# DSP_GPIO_Part2.net
KiCad netlist of a schematic drawn in Altium Designer
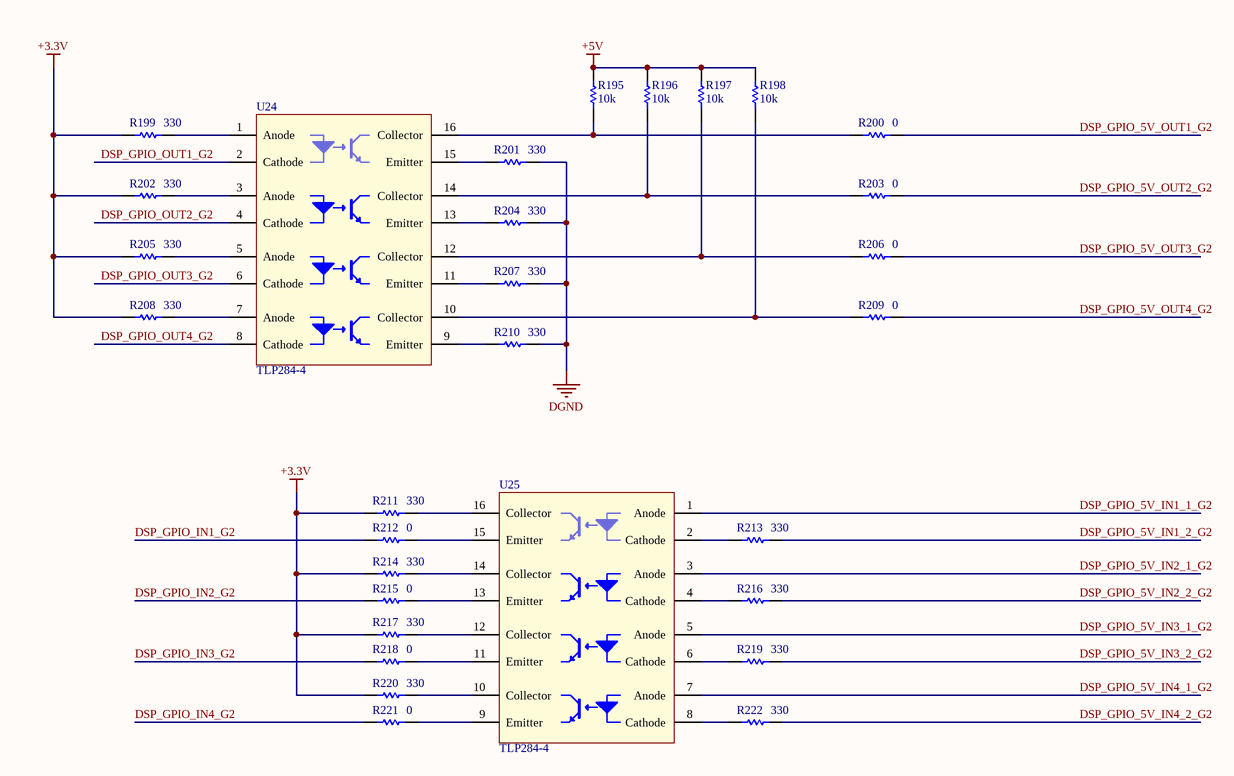
[diagram p0: DSP_GPIO_Part2.SchDoc]

(export (version "E")
  (design (tool "Eeschema 10.0.6"))
  (components
    (comp (ref "R195")
      (value "10k")
      (footprint "1608[0603]")
      (description "Resistor")
      (fields (field (name "Comment") "Res1") (field (name "PUBLISHER") "Altium Limited"))
      (libsource (lib "Miscellaneous Devices") (part "Res1"))
    )
    (comp (ref "R196")
      (value "10k")
      (footprint "1608[0603]")
      (description "Resistor")
      (fields (field (name "Comment") "Res1") (field (name "PUBLISHER") "Altium Limited"))
      (libsource (lib "Miscellaneous Devices") (part "Res1"))
    )
    (comp (ref "R197")
      (value "10k")
      (footprint "1608[0603]")
      (description "Resistor")
      (fields (field (name "Comment") "Res1") (field (name "PUBLISHER") "Altium Limited"))
      (libsource (lib "Miscellaneous Devices") (part "Res1"))
    )
    (comp (ref "R198")
      (value "10k")
      (footprint "1608[0603]")
      (description "Resistor")
      (fields (field (name "Comment") "Res1") (field (name "PUBLISHER") "Altium Limited"))
      (libsource (lib "Miscellaneous Devices") (part "Res1"))
    )
    (comp (ref "R199")
      (value "330")
      (footprint "1608[0603]")
      (description "Resistor")
      (fields (field (name "Comment") "Res1") (field (name "PUBLISHER") "Altium Limited"))
      (libsource (lib "Miscellaneous Devices") (part "Res1"))
    )
    (comp (ref "R200")
      (value "0")
      (footprint "1608[0603]")
      (description "Resistor")
      (fields (field (name "Comment") "Res1") (field (name "PUBLISHER") "Altium Limited"))
      (libsource (lib "Miscellaneous Devices") (part "Res1"))
    )
    (comp (ref "R201")
      (value "330")
      (footprint "1608[0603]")
      (description "Resistor")
      (fields (field (name "Comment") "Res1") (field (name "PUBLISHER") "Altium Limited"))
      (libsource (lib "Miscellaneous Devices") (part "Res1"))
    )
    (comp (ref "R202")
      (value "330")
      (footprint "1608[0603]")
      (description "Resistor")
      (fields (field (name "Comment") "Res1") (field (name "PUBLISHER") "Altium Limited"))
      (libsource (lib "Miscellaneous Devices") (part "Res1"))
    )
    (comp (ref "R203")
      (value "0")
      (footprint "1608[0603]")
      (description "Resistor")
      (fields (field (name "Comment") "Res1") (field (name "PUBLISHER") "Altium Limited"))
      (libsource (lib "Miscellaneous Devices") (part "Res1"))
    )
    (comp (ref "R204")
      (value "330")
      (footprint "1608[0603]")
      (description "Resistor")
      (fields (field (name "Comment") "Res1") (field (name "PUBLISHER") "Altium Limited"))
      (libsource (lib "Miscellaneous Devices") (part "Res1"))
    )
    (comp (ref "R205")
      (value "330")
      (footprint "1608[0603]")
      (description "Resistor")
      (fields (field (name "Comment") "Res1") (field (name "PUBLISHER") "Altium Limited"))
      (libsource (lib "Miscellaneous Devices") (part "Res1"))
    )
    (comp (ref "R206")
      (value "0")
      (footprint "1608[0603]")
      (description "Resistor")
      (fields (field (name "Comment") "Res1") (field (name "PUBLISHER") "Altium Limited"))
      (libsource (lib "Miscellaneous Devices") (part "Res1"))
    )
    (comp (ref "R207")
      (value "330")
      (footprint "1608[0603]")
      (description "Resistor")
      (fields (field (name "Comment") "Res1") (field (name "PUBLISHER") "Altium Limited"))
      (libsource (lib "Miscellaneous Devices") (part "Res1"))
    )
    (comp (ref "R208")
      (value "330")
      (footprint "1608[0603]")
      (description "Resistor")
      (fields (field (name "Comment") "Res1") (field (name "PUBLISHER") "Altium Limited"))
      (libsource (lib "Miscellaneous Devices") (part "Res1"))
    )
    (comp (ref "R209")
      (value "0")
      (footprint "1608[0603]")
      (description "Resistor")
      (fields (field (name "Comment") "Res1") (field (name "PUBLISHER") "Altium Limited"))
      (libsource (lib "Miscellaneous Devices") (part "Res1"))
    )
    (comp (ref "R210")
      (value "330")
      (footprint "1608[0603]")
      (description "Resistor")
      (fields (field (name "Comment") "Res1") (field (name "PUBLISHER") "Altium Limited"))
      (libsource (lib "Miscellaneous Devices") (part "Res1"))
    )
    (comp (ref "R211")
      (value "330")
      (footprint "1608[0603]")
      (description "Resistor")
      (fields (field (name "Comment") "Res1") (field (name "PUBLISHER") "Altium Limited"))
      (libsource (lib "Miscellaneous Devices") (part "Res1"))
    )
    (comp (ref "R212")
      (value "0")
      (footprint "1608[0603]")
      (description "Resistor")
      (fields (field (name "Comment") "Res1") (field (name "PUBLISHER") "Altium Limited"))
      (libsource (lib "Miscellaneous Devices") (part "Res1"))
    )
    (comp (ref "R213")
      (value "330")
      (footprint "1608[0603]")
      (description "Resistor")
      (fields (field (name "Comment") "Res1") (field (name "PUBLISHER") "Altium Limited"))
      (libsource (lib "Miscellaneous Devices") (part "Res1"))
    )
    (comp (ref "R214")
      (value "330")
      (footprint "1608[0603]")
      (description "Resistor")
      (fields (field (name "Comment") "Res1") (field (name "PUBLISHER") "Altium Limited"))
      (libsource (lib "Miscellaneous Devices") (part "Res1"))
    )
    (comp (ref "R215")
      (value "0")
      (footprint "1608[0603]")
      (description "Resistor")
      (fields (field (name "Comment") "Res1") (field (name "PUBLISHER") "Altium Limited"))
      (libsource (lib "Miscellaneous Devices") (part "Res1"))
    )
    (comp (ref "R216")
      (value "330")
      (footprint "1608[0603]")
      (description "Resistor")
      (fields (field (name "Comment") "Res1") (field (name "PUBLISHER") "Altium Limited"))
      (libsource (lib "Miscellaneous Devices") (part "Res1"))
    )
    (comp (ref "R217")
      (value "330")
      (footprint "1608[0603]")
      (description "Resistor")
      (fields (field (name "Comment") "Res1") (field (name "PUBLISHER") "Altium Limited"))
      (libsource (lib "Miscellaneous Devices") (part "Res1"))
    )
    (comp (ref "R218")
      (value "0")
      (footprint "1608[0603]")
      (description "Resistor")
      (fields (field (name "Comment") "Res1") (field (name "PUBLISHER") "Altium Limited"))
      (libsource (lib "Miscellaneous Devices") (part "Res1"))
    )
    (comp (ref "R219")
      (value "330")
      (footprint "1608[0603]")
      (description "Resistor")
      (fields (field (name "Comment") "Res1") (field (name "PUBLISHER") "Altium Limited"))
      (libsource (lib "Miscellaneous Devices") (part "Res1"))
    )
    (comp (ref "R220")
      (value "330")
      (footprint "1608[0603]")
      (description "Resistor")
      (fields (field (name "Comment") "Res1") (field (name "PUBLISHER") "Altium Limited"))
      (libsource (lib "Miscellaneous Devices") (part "Res1"))
    )
    (comp (ref "R221")
      (value "0")
      (footprint "1608[0603]")
      (description "Resistor")
      (fields (field (name "Comment") "Res1") (field (name "PUBLISHER") "Altium Limited"))
      (libsource (lib "Miscellaneous Devices") (part "Res1"))
    )
    (comp (ref "R222")
      (value "330")
      (footprint "1608[0603]")
      (description "Resistor")
      (fields (field (name "Comment") "Res1") (field (name "PUBLISHER") "Altium Limited"))
      (libsource (lib "Miscellaneous Devices") (part "Res1"))
    )
    (comp (ref "U24")
      (value "TLP284-4")
      (footprint "TLP284-4")
      (libsource (lib "DSP_FPGA_Lib") (part "TLP284-4"))
    )
    (comp (ref "U25")
      (value "TLP284-4")
      (footprint "TLP284-4")
      (libsource (lib "DSP_FPGA_Lib") (part "TLP284-4"))
    )
  )
  (nets
    (net (code "1") (name "+3.3V") (class "Default")
      (node (ref "R199") (pin "1") (pinfunction "1_1") (pintype "passive"))
      (node (ref "R202") (pin "1") (pinfunction "1_1") (pintype "passive"))
      (node (ref "R205") (pin "1") (pinfunction "1_1") (pintype "passive"))
      (node (ref "R208") (pin "1") (pinfunction "1_1") (pintype "passive"))
      (node (ref "R211") (pin "1") (pinfunction "1_1") (pintype "passive"))
      (node (ref "R214") (pin "1") (pinfunction "1_1") (pintype "passive"))
      (node (ref "R217") (pin "1") (pinfunction "1_1") (pintype "passive"))
      (node (ref "R220") (pin "1") (pinfunction "1_1") (pintype "passive"))
    )
    (net (code "2") (name "+5V") (class "Default")
      (node (ref "R195") (pin "2") (pinfunction "2_2") (pintype "passive"))
      (node (ref "R196") (pin "2") (pinfunction "2_2") (pintype "passive"))
      (node (ref "R197") (pin "2") (pinfunction "2_2") (pintype "passive"))
      (node (ref "R198") (pin "2") (pinfunction "2_2") (pintype "passive"))
    )
    (net (code "3") (name "/DSP_GPIO_5V_IN1_1_G2") (class "Default")
      (node (ref "U25") (pin "1") (pinfunction "Anode_1") (pintype "passive"))
    )
    (net (code "4") (name "/DSP_GPIO_5V_IN1_2_G2") (class "Default")
      (node (ref "R213") (pin "2") (pinfunction "2_2") (pintype "passive"))
    )
    (net (code "5") (name "/DSP_GPIO_5V_IN2_1_G2") (class "Default")
      (node (ref "U25") (pin "3") (pinfunction "Anode_3") (pintype "passive"))
    )
    (net (code "6") (name "/DSP_GPIO_5V_IN2_2_G2") (class "Default")
      (node (ref "R216") (pin "2") (pinfunction "2_2") (pintype "passive"))
    )
    (net (code "7") (name "/DSP_GPIO_5V_IN3_1_G2") (class "Default")
      (node (ref "U25") (pin "5") (pinfunction "Anode_5") (pintype "passive"))
    )
    (net (code "8") (name "/DSP_GPIO_5V_IN3_2_G2") (class "Default")
      (node (ref "R219") (pin "2") (pinfunction "2_2") (pintype "passive"))
    )
    (net (code "9") (name "/DSP_GPIO_5V_IN4_1_G2") (class "Default")
      (node (ref "U25") (pin "7") (pinfunction "Anode_7") (pintype "passive"))
    )
    (net (code "10") (name "/DSP_GPIO_5V_IN4_2_G2") (class "Default")
      (node (ref "R222") (pin "2") (pinfunction "2_2") (pintype "passive"))
    )
    (net (code "11") (name "/DSP_GPIO_5V_OUT1_G2") (class "Default")
      (node (ref "R200") (pin "2") (pinfunction "2_2") (pintype "passive"))
    )
    (net (code "12") (name "/DSP_GPIO_5V_OUT2_G2") (class "Default")
      (node (ref "R203") (pin "2") (pinfunction "2_2") (pintype "passive"))
    )
    (net (code "13") (name "/DSP_GPIO_5V_OUT3_G2") (class "Default")
      (node (ref "R206") (pin "2") (pinfunction "2_2") (pintype "passive"))
    )
    (net (code "14") (name "/DSP_GPIO_5V_OUT4_G2") (class "Default")
      (node (ref "R209") (pin "2") (pinfunction "2_2") (pintype "passive"))
    )
    (net (code "15") (name "/DSP_GPIO_IN1_G2") (class "Default")
      (node (ref "R212") (pin "1") (pinfunction "1_1") (pintype "passive"))
    )
    (net (code "16") (name "/DSP_GPIO_IN2_G2") (class "Default")
      (node (ref "R215") (pin "1") (pinfunction "1_1") (pintype "passive"))
    )
    (net (code "17") (name "/DSP_GPIO_IN3_G2") (class "Default")
      (node (ref "R218") (pin "1") (pinfunction "1_1") (pintype "passive"))
    )
    (net (code "18") (name "/DSP_GPIO_IN4_G2") (class "Default")
      (node (ref "R221") (pin "1") (pinfunction "1_1") (pintype "passive"))
    )
    (net (code "19") (name "/DSP_GPIO_OUT1_G2") (class "Default")
      (node (ref "U24") (pin "2") (pinfunction "Cathode_2") (pintype "passive"))
    )
    (net (code "20") (name "/DSP_GPIO_OUT2_G2") (class "Default")
      (node (ref "U24") (pin "4") (pinfunction "Cathode_4") (pintype "passive"))
    )
    (net (code "21") (name "/DSP_GPIO_OUT3_G2") (class "Default")
      (node (ref "U24") (pin "6") (pinfunction "Cathode_6") (pintype "passive"))
    )
    (net (code "22") (name "/DSP_GPIO_OUT4_G2") (class "Default")
      (node (ref "U24") (pin "8") (pinfunction "Cathode_8") (pintype "passive"))
    )
    (net (code "23") (name "DGND") (class "Default")
      (node (ref "R201") (pin "2") (pinfunction "2_2") (pintype "passive"))
      (node (ref "R204") (pin "2") (pinfunction "2_2") (pintype "passive"))
      (node (ref "R207") (pin "2") (pinfunction "2_2") (pintype "passive"))
      (node (ref "R210") (pin "2") (pinfunction "2_2") (pintype "passive"))
    )
    (net (code "24") (name "Net-(R195-Pad1)") (class "Default")
      (node (ref "R195") (pin "1") (pinfunction "1_1") (pintype "passive"))
      (node (ref "R200") (pin "1") (pinfunction "1_1") (pintype "passive"))
      (node (ref "U24") (pin "16") (pinfunction "Collector_16") (pintype "passive"))
    )
    (net (code "25") (name "Net-(R196-Pad1)") (class "Default")
      (node (ref "R196") (pin "1") (pinfunction "1_1") (pintype "passive"))
      (node (ref "R203") (pin "1") (pinfunction "1_1") (pintype "passive"))
      (node (ref "U24") (pin "14") (pinfunction "Collector_14") (pintype "passive"))
    )
    (net (code "26") (name "Net-(R197-Pad1)") (class "Default")
      (node (ref "R197") (pin "1") (pinfunction "1_1") (pintype "passive"))
      (node (ref "R206") (pin "1") (pinfunction "1_1") (pintype "passive"))
      (node (ref "U24") (pin "12") (pinfunction "Collector_12") (pintype "passive"))
    )
    (net (code "27") (name "Net-(R198-Pad1)") (class "Default")
      (node (ref "R198") (pin "1") (pinfunction "1_1") (pintype "passive"))
      (node (ref "R209") (pin "1") (pinfunction "1_1") (pintype "passive"))
      (node (ref "U24") (pin "10") (pinfunction "Collector_10") (pintype "passive"))
    )
    (net (code "28") (name "Net-(R199-Pad2)") (class "Default")
      (node (ref "R199") (pin "2") (pinfunction "2_2") (pintype "passive"))
      (node (ref "U24") (pin "1") (pinfunction "Anode_1") (pintype "passive"))
    )
    (net (code "29") (name "Net-(R201-Pad1)") (class "Default")
      (node (ref "R201") (pin "1") (pinfunction "1_1") (pintype "passive"))
      (node (ref "U24") (pin "15") (pinfunction "Emitter_15") (pintype "passive"))
    )
    (net (code "30") (name "Net-(R202-Pad2)") (class "Default")
      (node (ref "R202") (pin "2") (pinfunction "2_2") (pintype "passive"))
      (node (ref "U24") (pin "3") (pinfunction "Anode_3") (pintype "passive"))
    )
    (net (code "31") (name "Net-(R204-Pad1)") (class "Default")
      (node (ref "R204") (pin "1") (pinfunction "1_1") (pintype "passive"))
      (node (ref "U24") (pin "13") (pinfunction "Emitter_13") (pintype "passive"))
    )
    (net (code "32") (name "Net-(R205-Pad2)") (class "Default")
      (node (ref "R205") (pin "2") (pinfunction "2_2") (pintype "passive"))
      (node (ref "U24") (pin "5") (pinfunction "Anode_5") (pintype "passive"))
    )
    (net (code "33") (name "Net-(R207-Pad1)") (class "Default")
      (node (ref "R207") (pin "1") (pinfunction "1_1") (pintype "passive"))
      (node (ref "U24") (pin "11") (pinfunction "Emitter_11") (pintype "passive"))
    )
    (net (code "34") (name "Net-(R208-Pad2)") (class "Default")
      (node (ref "R208") (pin "2") (pinfunction "2_2") (pintype "passive"))
      (node (ref "U24") (pin "7") (pinfunction "Anode_7") (pintype "passive"))
    )
    (net (code "35") (name "Net-(R210-Pad1)") (class "Default")
      (node (ref "R210") (pin "1") (pinfunction "1_1") (pintype "passive"))
      (node (ref "U24") (pin "9") (pinfunction "Emitter_9") (pintype "passive"))
    )
    (net (code "36") (name "Net-(R211-Pad2)") (class "Default")
      (node (ref "R211") (pin "2") (pinfunction "2_2") (pintype "passive"))
      (node (ref "U25") (pin "16") (pinfunction "Collector_16") (pintype "passive"))
    )
    (net (code "37") (name "Net-(R212-Pad2)") (class "Default")
      (node (ref "R212") (pin "2") (pinfunction "2_2") (pintype "passive"))
      (node (ref "U25") (pin "15") (pinfunction "Emitter_15") (pintype "passive"))
    )
    (net (code "38") (name "Net-(R213-Pad1)") (class "Default")
      (node (ref "R213") (pin "1") (pinfunction "1_1") (pintype "passive"))
      (node (ref "U25") (pin "2") (pinfunction "Cathode_2") (pintype "passive"))
    )
    (net (code "39") (name "Net-(R214-Pad2)") (class "Default")
      (node (ref "R214") (pin "2") (pinfunction "2_2") (pintype "passive"))
      (node (ref "U25") (pin "14") (pinfunction "Collector_14") (pintype "passive"))
    )
    (net (code "40") (name "Net-(R215-Pad2)") (class "Default")
      (node (ref "R215") (pin "2") (pinfunction "2_2") (pintype "passive"))
      (node (ref "U25") (pin "13") (pinfunction "Emitter_13") (pintype "passive"))
    )
    (net (code "41") (name "Net-(R216-Pad1)") (class "Default")
      (node (ref "R216") (pin "1") (pinfunction "1_1") (pintype "passive"))
      (node (ref "U25") (pin "4") (pinfunction "Cathode_4") (pintype "passive"))
    )
    (net (code "42") (name "Net-(R217-Pad2)") (class "Default")
      (node (ref "R217") (pin "2") (pinfunction "2_2") (pintype "passive"))
      (node (ref "U25") (pin "12") (pinfunction "Collector_12") (pintype "passive"))
    )
    (net (code "43") (name "Net-(R218-Pad2)") (class "Default")
      (node (ref "R218") (pin "2") (pinfunction "2_2") (pintype "passive"))
      (node (ref "U25") (pin "11") (pinfunction "Emitter_11") (pintype "passive"))
    )
    (net (code "44") (name "Net-(R219-Pad1)") (class "Default")
      (node (ref "R219") (pin "1") (pinfunction "1_1") (pintype "passive"))
      (node (ref "U25") (pin "6") (pinfunction "Cathode_6") (pintype "passive"))
    )
    (net (code "45") (name "Net-(R220-Pad2)") (class "Default")
      (node (ref "R220") (pin "2") (pinfunction "2_2") (pintype "passive"))
      (node (ref "U25") (pin "10") (pinfunction "Collector_10") (pintype "passive"))
    )
    (net (code "46") (name "Net-(R221-Pad2)") (class "Default")
      (node (ref "R221") (pin "2") (pinfunction "2_2") (pintype "passive"))
      (node (ref "U25") (pin "9") (pinfunction "Emitter_9") (pintype "passive"))
    )
    (net (code "47") (name "Net-(R222-Pad1)") (class "Default")
      (node (ref "R222") (pin "1") (pinfunction "1_1") (pintype "passive"))
      (node (ref "U25") (pin "8") (pinfunction "Cathode_8") (pintype "passive"))
    )
  )
)
